# Hutschienenmoped_12V.net
KiCad netlist of a schematic drawn in EAGLE
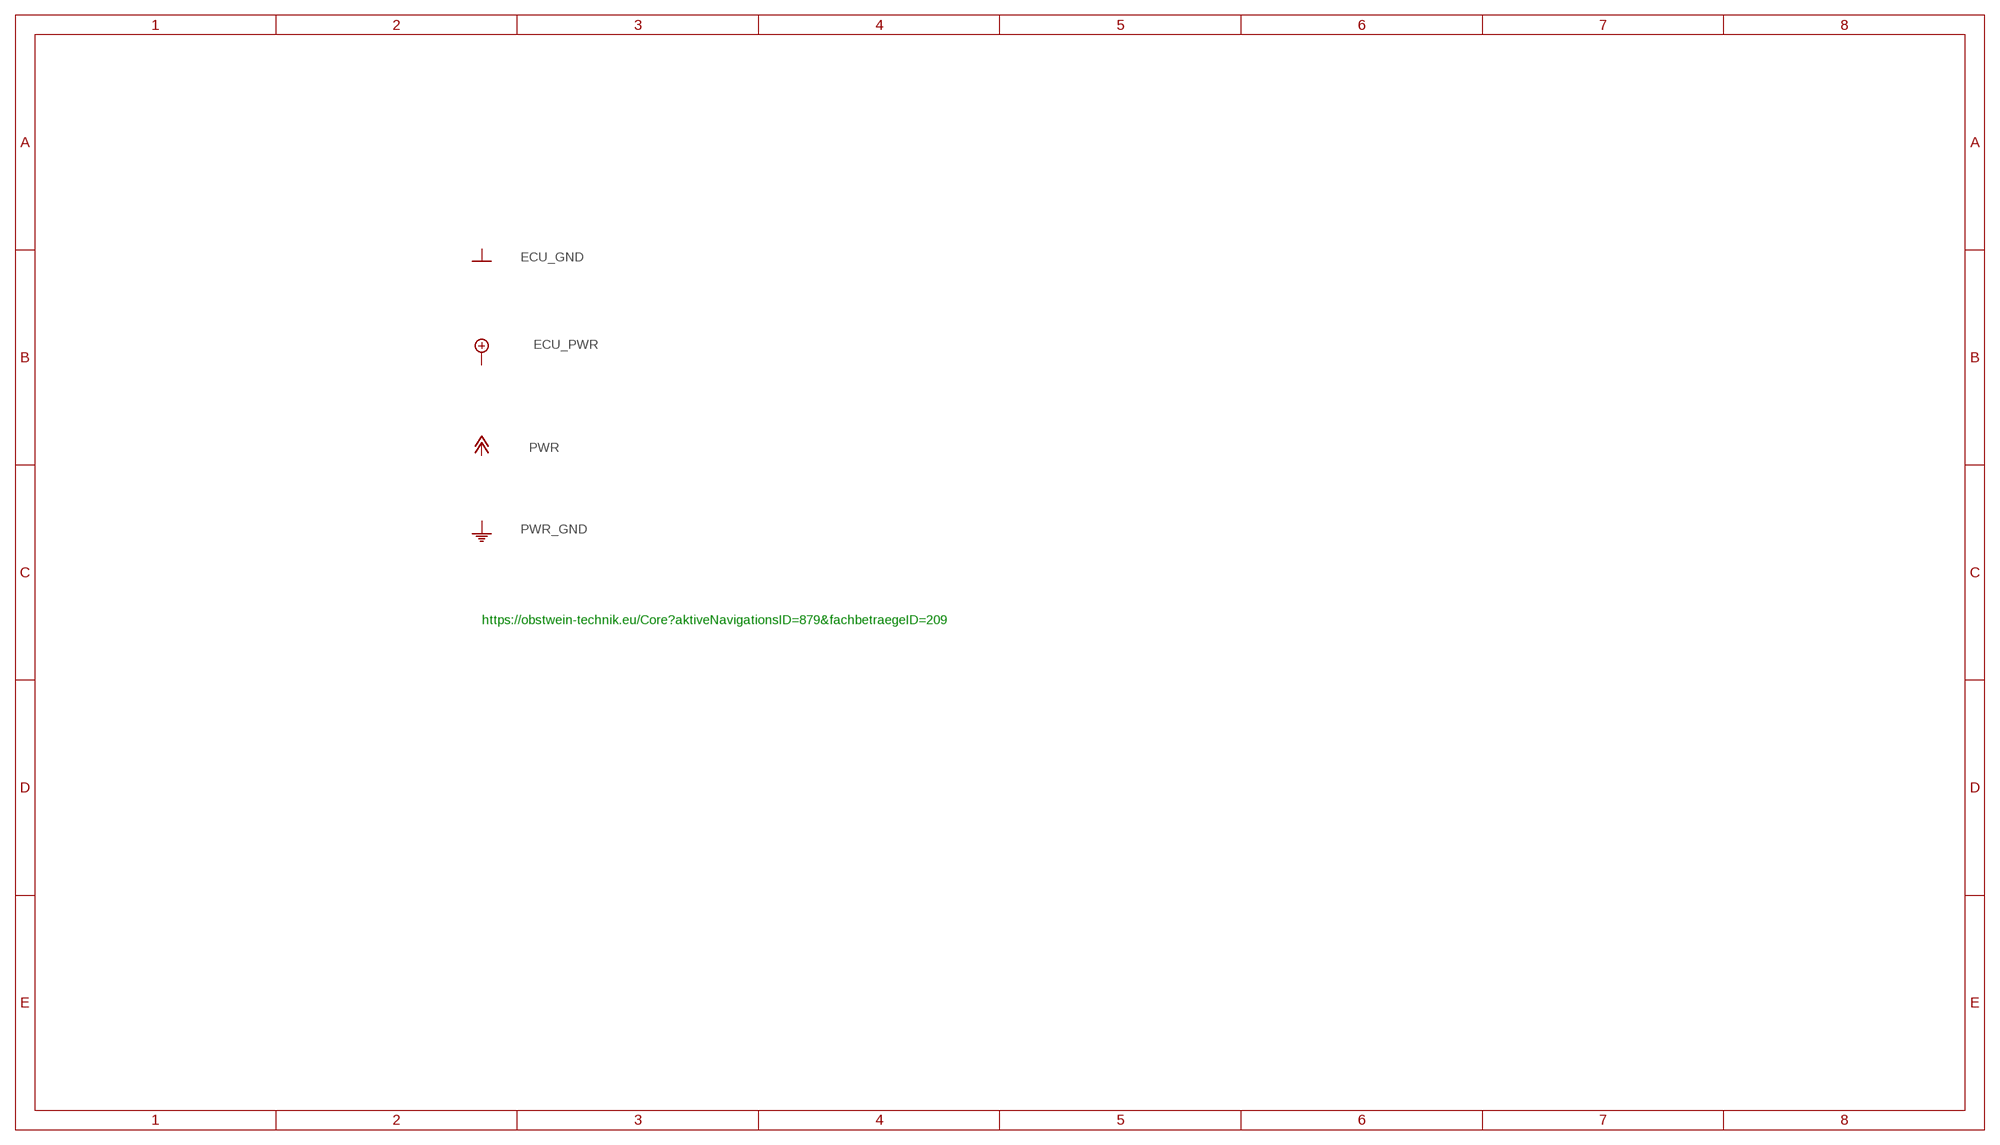
[diagram p0: schematic, sheet 1]
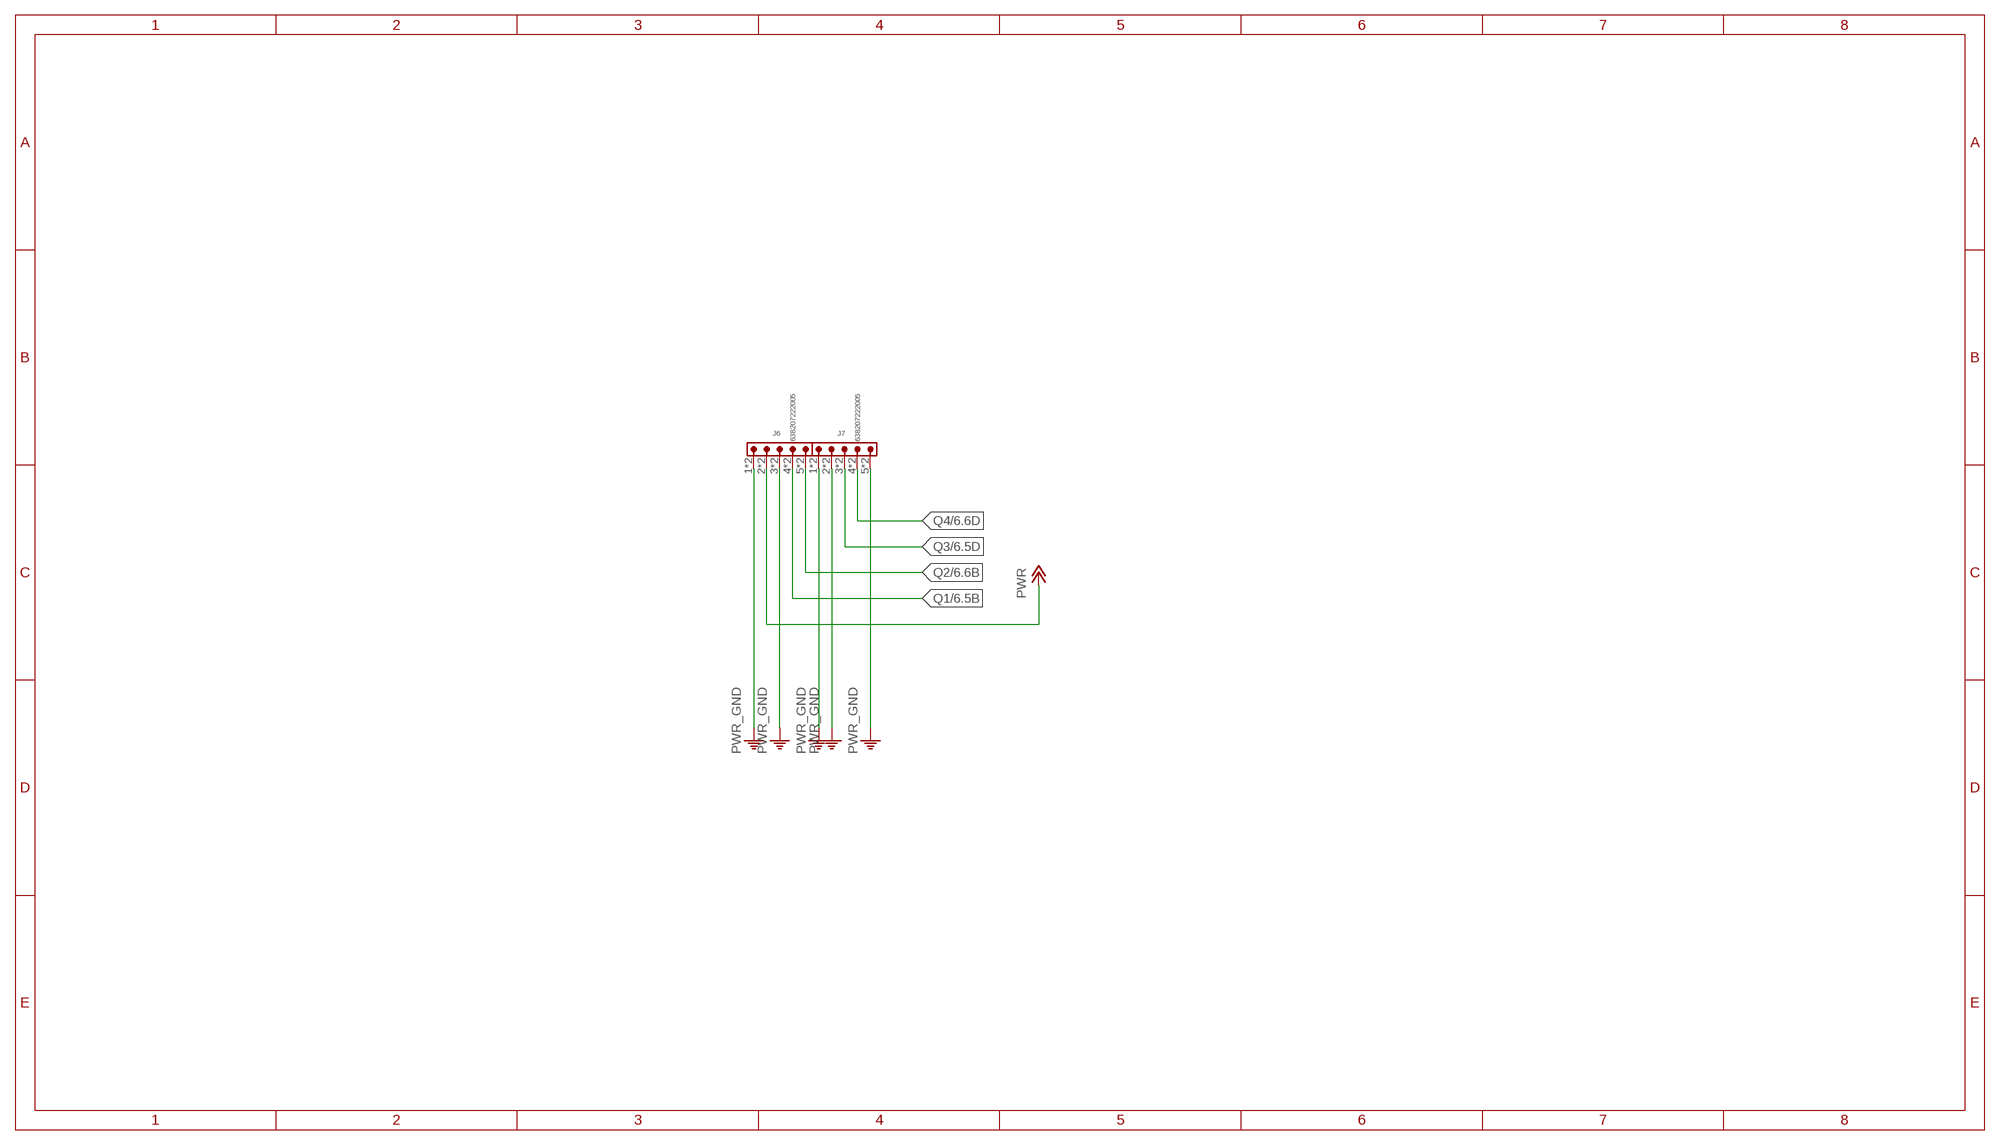
[diagram p1: schematic, sheet 2]
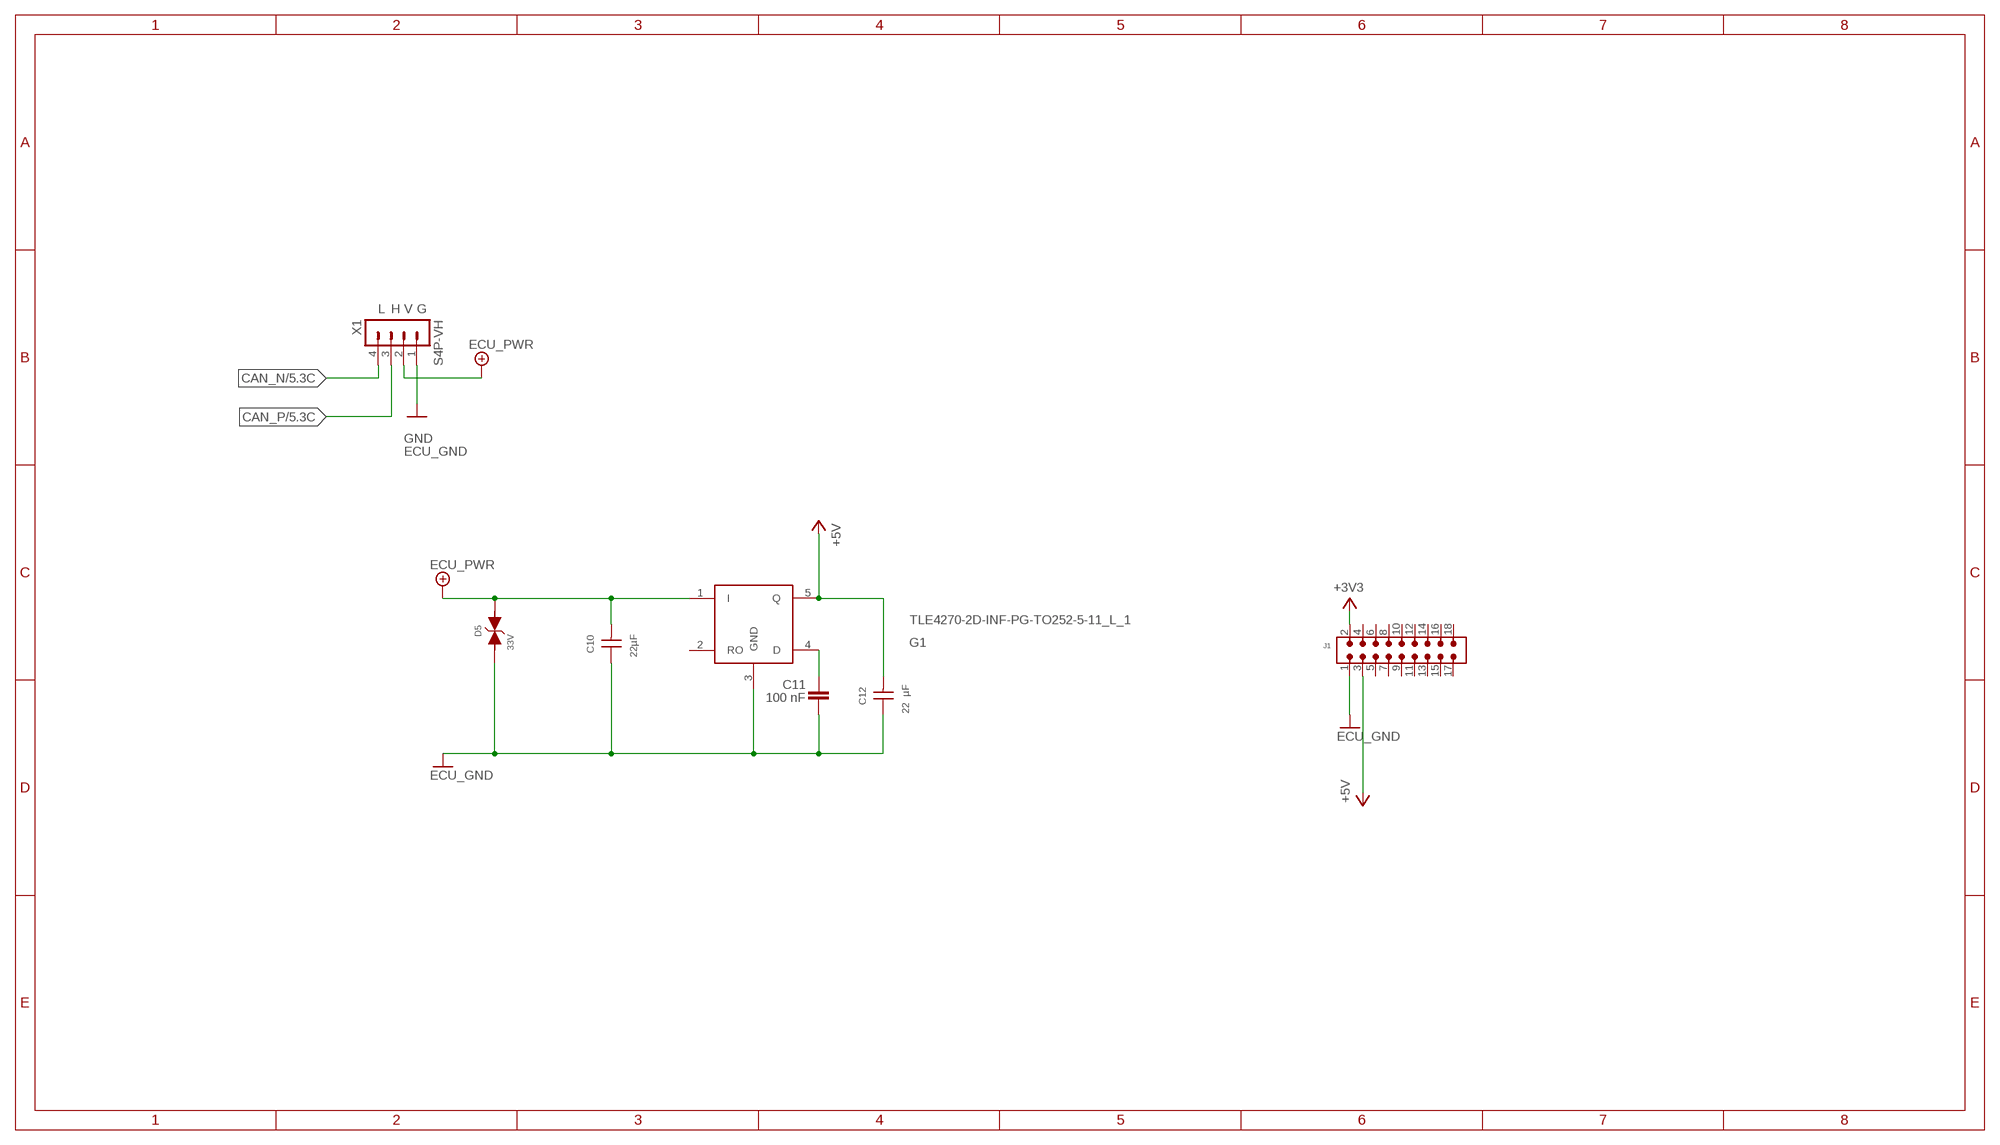
[diagram p2: schematic, sheet 3]
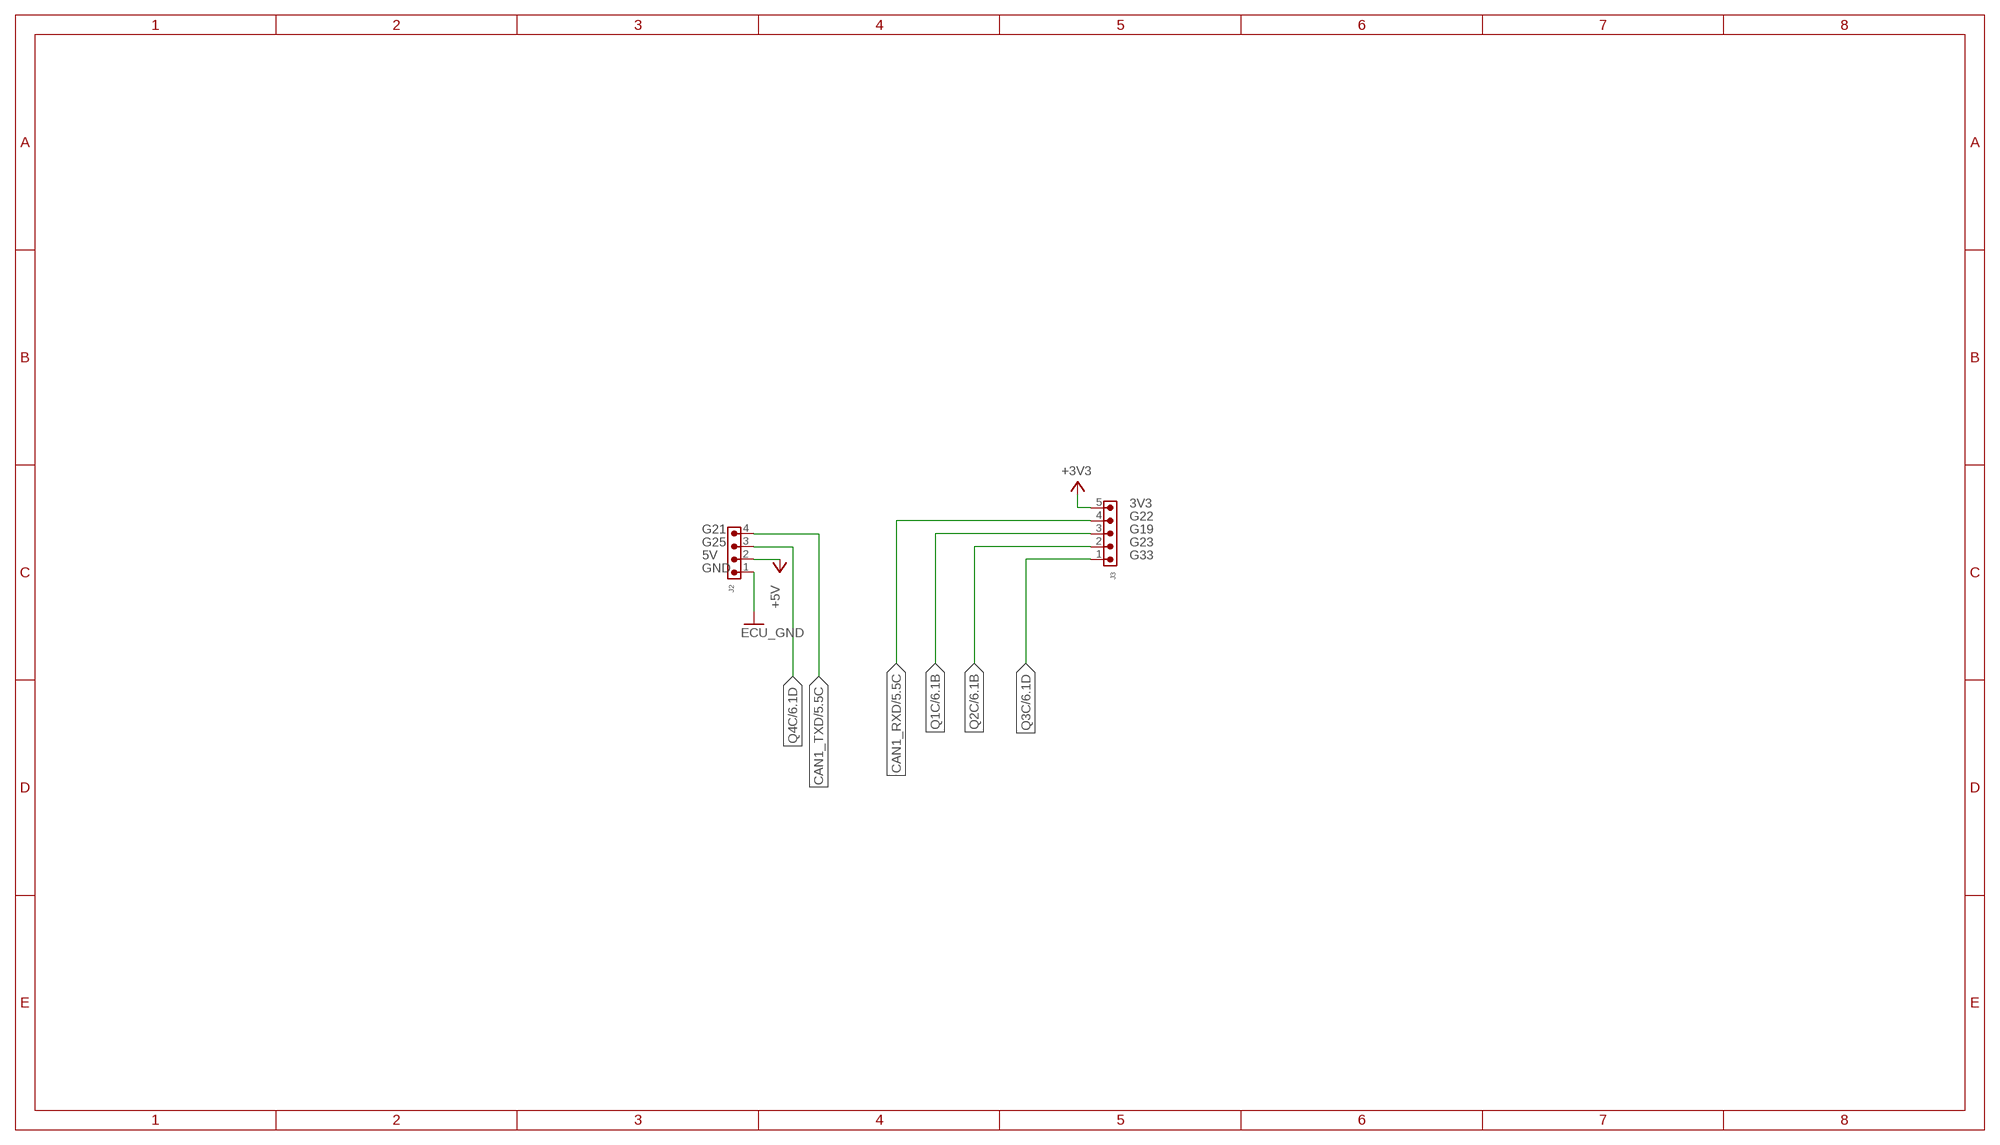
[diagram p3: schematic, sheet 4]
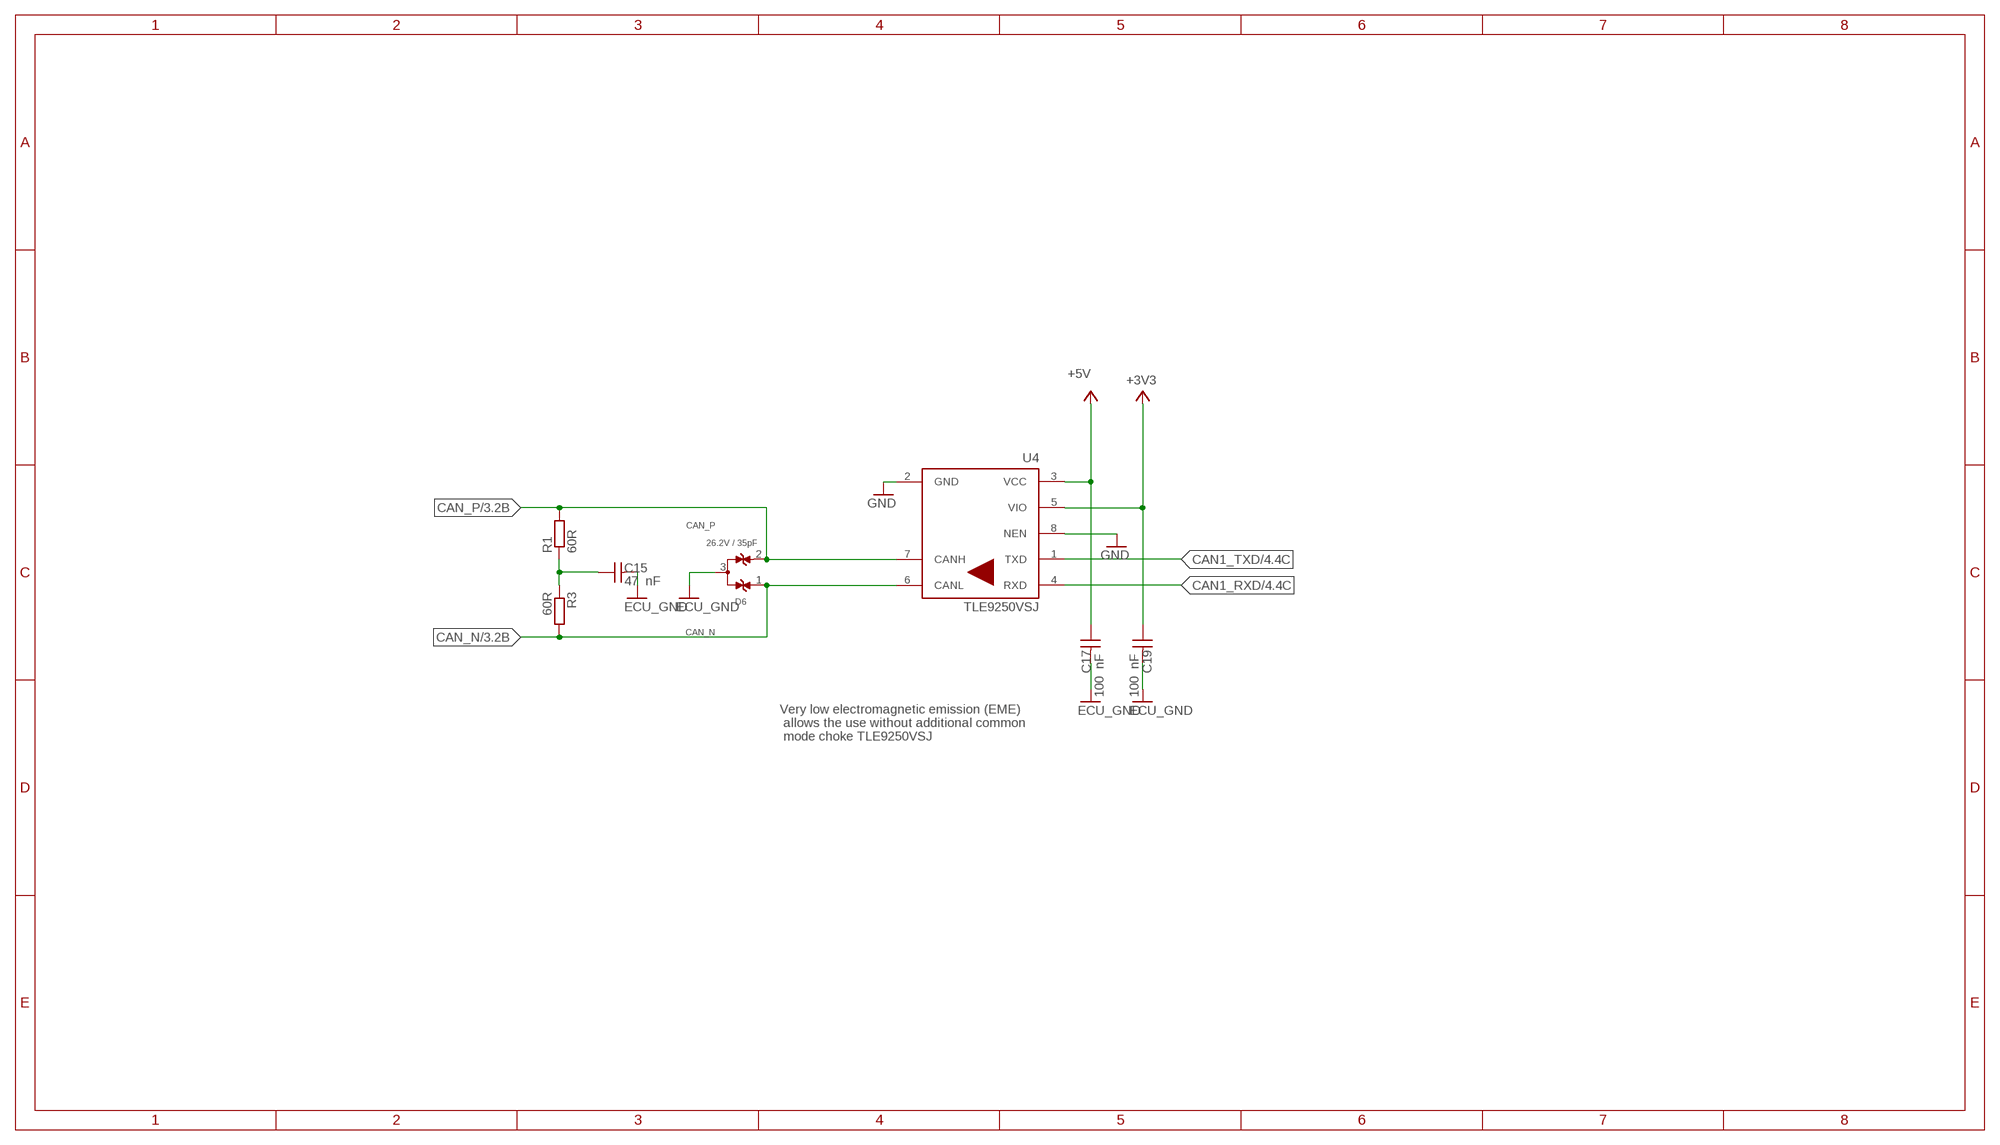
[diagram p4: schematic, sheet 5]
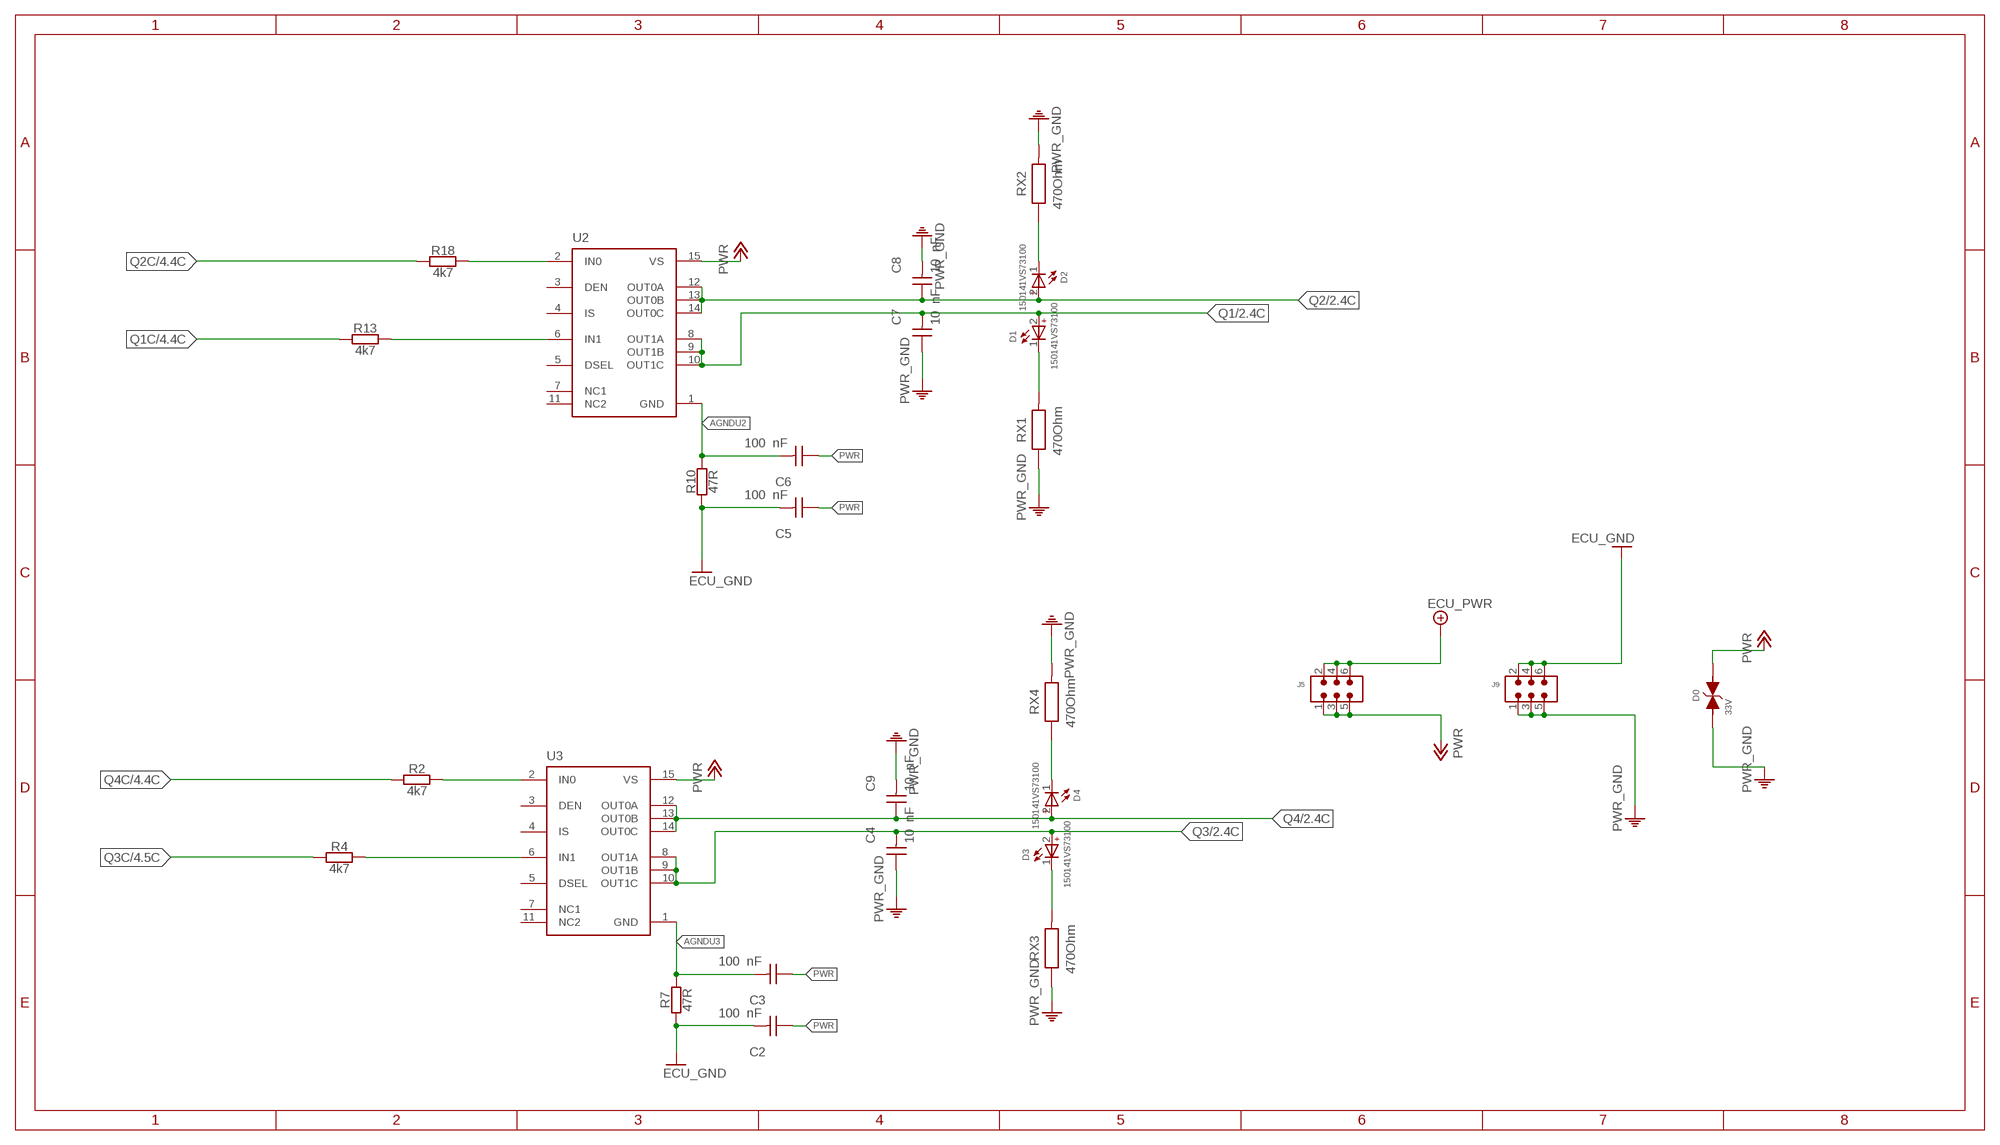
[diagram p5: schematic, sheet 6]

(export (version "E")
  (design (tool "Eeschema 10.0.6"))
  (components
    (comp (ref "C10")
      (value "22µF")
      (footprint "eagle-import:WCAP-CSGP_1210_H2.5")
      (libsource (lib "eagle-import") (part "WCAP-CSGP_1210_H2.5_25V(DC)_885012109014"))
    )
    (comp (ref "C11")
      (value "100 nF")
      (footprint "eagle-import:WCAP-CSGP_0402")
      (libsource (lib "eagle-import") (part "WCAP-CSGP_0402_16V(DC)_885012205037"))
    )
    (comp (ref "C12")
      (value "22 µF")
      (footprint "eagle-import:WCAP-CSGP_0805_H1.25_R")
      (libsource (lib "eagle-import") (part "WCAP-CSGP_0805_H1.25_10V(DC)_885012107011"))
    )
    (comp (ref "D5")
      (value "33V")
      (footprint "eagle-import:WE-TVSP_DO-214AB_BIDIRECTIONAL")
      (libsource (lib "eagle-import") (part "WE-TVSP_DO-214AB_3000W_BI_824551331"))
    )
    (comp (ref "G1")
      (value "TLE4270-2D-INF-PG-TO252-5-11_L_1")
      (footprint "eagle-import:INF-PG-TO252-5-11_L_1PRIMARY")
      (libsource (lib "eagle-import") (part "TLE4270-2D-INF-PG-TO252-5-11_L_1"))
    )
    (comp (ref "J1")
      (value "6130XX21121_61301821121")
      (footprint "eagle-import:61301821121")
      (libsource (lib "eagle-import") (part "6130XX21121_61301821121"))
    )
    (comp (ref "X1")
      (value "S4P-VH")
      (footprint "eagle-import:S4P-VH")
      (libsource (lib "eagle-import") (part "S4P-VH"))
    )
    (comp (ref "J6")
      (value "638207222005")
      (footprint "eagle-import:638207222005")
      (libsource (lib "eagle-import") (part "638207222005"))
    )
    (comp (ref "J7")
      (value "638207222005")
      (footprint "eagle-import:638207222005")
      (libsource (lib "eagle-import") (part "638207222005"))
    )
    (comp (ref "C2")
      (value "100 nF")
      (footprint "eagle-import:WCAP-CSGP_0805_H0.8_R")
      (libsource (lib "eagle-import") (part "WCAP-CSGP_0805_H0.8_50V(DC)_R_885012207098"))
    )
    (comp (ref "C3")
      (value "100 nF")
      (footprint "eagle-import:WCAP-CSGP_0805_H0.8_R")
      (libsource (lib "eagle-import") (part "WCAP-CSGP_0805_H0.8_50V(DC)_R_885012207098"))
    )
    (comp (ref "C4")
      (value "10 nF")
      (footprint "eagle-import:WCAP-CSGP_0805_H0.8_R")
      (libsource (lib "eagle-import") (part "WCAP-CSGP_0805_H0.8_50V(DC)_R_885012207092"))
    )
    (comp (ref "C5")
      (value "100 nF")
      (footprint "eagle-import:WCAP-CSGP_0805_H0.8_R")
      (libsource (lib "eagle-import") (part "WCAP-CSGP_0805_H0.8_50V(DC)_R_885012207098"))
    )
    (comp (ref "C6")
      (value "100 nF")
      (footprint "eagle-import:WCAP-CSGP_0805_H0.8_R")
      (libsource (lib "eagle-import") (part "WCAP-CSGP_0805_H0.8_50V(DC)_R_885012207098"))
    )
    (comp (ref "C7")
      (value "10 nF")
      (footprint "eagle-import:WCAP-CSGP_0805_H0.8_R")
      (libsource (lib "eagle-import") (part "WCAP-CSGP_0805_H0.8_50V(DC)_R_885012207092"))
    )
    (comp (ref "C8")
      (value "10 nF")
      (footprint "eagle-import:WCAP-CSGP_0805_H0.8_R")
      (libsource (lib "eagle-import") (part "WCAP-CSGP_0805_H0.8_50V(DC)_R_885012207092"))
    )
    (comp (ref "C9")
      (value "10 nF")
      (footprint "eagle-import:WCAP-CSGP_0805_H0.8_R")
      (libsource (lib "eagle-import") (part "WCAP-CSGP_0805_H0.8_50V(DC)_R_885012207092"))
    )
    (comp (ref "D0")
      (value "33V")
      (footprint "eagle-import:WE-TVSP_DO-214AB_BIDIRECTIONAL")
      (libsource (lib "eagle-import") (part "WE-TVSP_DO-214AB_3000W_BI_824551331"))
    )
    (comp (ref "D1")
      (value "150141VS73100")
      (footprint "eagle-import:WL-SMTW_3528")
      (libsource (lib "eagle-import") (part "WL-SMTW_3528_150141VS73100"))
    )
    (comp (ref "D2")
      (value "150141VS73100")
      (footprint "eagle-import:WL-SMTW_3528")
      (libsource (lib "eagle-import") (part "WL-SMTW_3528_150141VS73100"))
    )
    (comp (ref "D3")
      (value "150141VS73100")
      (footprint "eagle-import:WL-SMTW_3528")
      (libsource (lib "eagle-import") (part "WL-SMTW_3528_150141VS73100"))
    )
    (comp (ref "D4")
      (value "150141VS73100")
      (footprint "eagle-import:WL-SMTW_3528")
      (libsource (lib "eagle-import") (part "WL-SMTW_3528_150141VS73100"))
    )
    (comp (ref "J5")
      (value "6130XX21121_61300621121")
      (footprint "eagle-import:61300621121")
      (libsource (lib "eagle-import") (part "6130XX21121_61300621121"))
    )
    (comp (ref "J9")
      (value "6130XX21121_61300621121")
      (footprint "eagle-import:61300621121")
      (libsource (lib "eagle-import") (part "6130XX21121_61300621121"))
    )
    (comp (ref "R2")
      (value "4k7")
      (footprint "eagle-import:R0805")
      (libsource (lib "eagle-import") (part "R-EU_R0805"))
    )
    (comp (ref "R4")
      (value "4k7")
      (footprint "eagle-import:R0805")
      (libsource (lib "eagle-import") (part "R-EU_R0805"))
    )
    (comp (ref "R7")
      (value "47R")
      (footprint "eagle-import:R0805")
      (libsource (lib "eagle-import") (part "R-EU_R0805"))
    )
    (comp (ref "R10")
      (value "47R")
      (footprint "eagle-import:R0805")
      (libsource (lib "eagle-import") (part "R-EU_R0805"))
    )
    (comp (ref "R13")
      (value "4k7")
      (footprint "eagle-import:R0805")
      (libsource (lib "eagle-import") (part "R-EU_R0805"))
    )
    (comp (ref "R18")
      (value "4k7")
      (footprint "eagle-import:R0805")
      (libsource (lib "eagle-import") (part "R-EU_R0805"))
    )
    (comp (ref "RX1")
      (value "470Ohm")
      (footprint "eagle-import:WRIS-KWKB_0612")
      (libsource (lib "eagle-import") (part "WRIS-KWKB_0612_561020132023"))
    )
    (comp (ref "RX2")
      (value "470Ohm")
      (footprint "eagle-import:WRIS-KWKB_0612")
      (libsource (lib "eagle-import") (part "WRIS-KWKB_0612_561020132023"))
    )
    (comp (ref "RX3")
      (value "470Ohm")
      (footprint "eagle-import:WRIS-KWKB_0612")
      (libsource (lib "eagle-import") (part "WRIS-KWKB_0612_561020132023"))
    )
    (comp (ref "RX4")
      (value "470Ohm")
      (footprint "eagle-import:WRIS-KWKB_0612")
      (libsource (lib "eagle-import") (part "WRIS-KWKB_0612_561020132023"))
    )
    (comp (ref "U2")
      (value "BTS7030-2EPA")
      (footprint "eagle-import:SOP65P600X115-15N-V")
      (libsource (lib "eagle-import") (part "BTS7030-2EPA"))
    )
    (comp (ref "U3")
      (value "BTS7030-2EPA")
      (footprint "eagle-import:SOP65P600X115-15N-V")
      (libsource (lib "eagle-import") (part "BTS7030-2EPA"))
    )
    (comp (ref "C15")
      (value "47 nF")
      (footprint "eagle-import:WCAP-CSGP_0805_H0.8_R")
      (libsource (lib "eagle-import") (part "WCAP-CSGP_0805_H0.8_50V(DC)_R_885012207096"))
    )
    (comp (ref "C17")
      (value "100 nF")
      (footprint "eagle-import:WCAP-CSGP_0805_H0.8_R")
      (libsource (lib "eagle-import") (part "WCAP-CSGP_0805_H0.8_50V(DC)_R_885012207098"))
    )
    (comp (ref "C19")
      (value "100 nF")
      (footprint "eagle-import:WCAP-CSGP_0805_H0.8_R")
      (libsource (lib "eagle-import") (part "WCAP-CSGP_0805_H0.8_50V(DC)_R_885012207098"))
    )
    (comp (ref "D6")
      (value "26.2V / 35pF")
      (footprint "eagle-import:WE-TVS_SOT23-3L")
      (libsource (lib "eagle-import") (part "WE-TVS_SOT23-3L_824098024"))
    )
    (comp (ref "R1")
      (value "60R")
      (footprint "eagle-import:R0805")
      (libsource (lib "eagle-import") (part "R-EU_R0805"))
    )
    (comp (ref "R3")
      (value "60R")
      (footprint "eagle-import:R0805")
      (libsource (lib "eagle-import") (part "R-EU_R0805"))
    )
    (comp (ref "U4")
      (value "TLE9250VSJ")
      (footprint "eagle-import:SOIC127P602X173-8N-V")
      (libsource (lib "eagle-import") (part "TLE9250VSJ"))
    )
    (comp (ref "J2")
      (value "6130XX11121_61300411121")
      (footprint "eagle-import:61300411121")
      (libsource (lib "eagle-import") (part "6130XX11121_61300411121"))
    )
    (comp (ref "J3")
      (value "6130XX11121_61300511121")
      (footprint "eagle-import:61300511121")
      (libsource (lib "eagle-import") (part "6130XX11121_61300511121"))
    )
  )
  (nets
    (net (code "1") (name "+3V3") (class "Default")
      (node (ref "C19") (pin "1") (pinfunction "1_1") (pintype "passive"))
      (node (ref "J1") (pin "2") (pinfunction "2_2") (pintype "passive"))
      (node (ref "J3") (pin "5") (pinfunction "5_5") (pintype "passive"))
      (node (ref "U4") (pin "5") (pinfunction "VIO_5") (pintype "input"))
    )
    (net (code "2") (name "+5V") (class "Default")
      (node (ref "C12") (pin "2") (pinfunction "2_2") (pintype "passive"))
      (node (ref "C17") (pin "1") (pinfunction "1_1") (pintype "passive"))
      (node (ref "G1") (pin "5") (pinfunction "Q_5") (pintype "power_in"))
      (node (ref "J1") (pin "3") (pinfunction "3_3") (pintype "passive"))
      (node (ref "J2") (pin "2") (pinfunction "2_2") (pintype "passive"))
      (node (ref "U4") (pin "3") (pinfunction "VCC_3") (pintype "input"))
    )
    (net (code "3") (name "AGNDU2") (class "Default")
      (node (ref "C6") (pin "2") (pinfunction "2_2") (pintype "passive"))
      (node (ref "R10") (pin "2") (pinfunction "2_2") (pintype "passive"))
      (node (ref "U2") (pin "1") (pinfunction "GND_1") (pintype "power_in"))
    )
    (net (code "4") (name "AGNDU3") (class "Default")
      (node (ref "C3") (pin "2") (pinfunction "2_2") (pintype "passive"))
      (node (ref "R7") (pin "2") (pinfunction "2_2") (pintype "passive"))
      (node (ref "U3") (pin "1") (pinfunction "GND_1") (pintype "power_in"))
    )
    (net (code "5") (name "CAN1_RXD") (class "Default")
      (node (ref "J3") (pin "4") (pinfunction "4_4") (pintype "passive"))
      (node (ref "U4") (pin "4") (pinfunction "RXD_4") (pintype "output"))
    )
    (net (code "6") (name "CAN1_TXD") (class "Default")
      (node (ref "J2") (pin "4") (pinfunction "4_4") (pintype "passive"))
      (node (ref "U4") (pin "1") (pinfunction "TXD_1") (pintype "input"))
    )
    (net (code "7") (name "CAN_N") (class "Default")
      (node (ref "D6") (pin "1") (pinfunction "1_1") (pintype "passive"))
      (node (ref "R3") (pin "2") (pinfunction "2_2") (pintype "passive"))
      (node (ref "U4") (pin "6") (pinfunction "CANL_6") (pintype "bidirectional"))
      (node (ref "X1") (pin "4") (pinfunction "4_4") (pintype "passive"))
    )
    (net (code "8") (name "CAN_P") (class "Default")
      (node (ref "D6") (pin "2") (pinfunction "2_2") (pintype "passive"))
      (node (ref "R1") (pin "2") (pinfunction "2_2") (pintype "passive"))
      (node (ref "U4") (pin "7") (pinfunction "CANH_7") (pintype "bidirectional"))
      (node (ref "X1") (pin "3") (pinfunction "3_3") (pintype "passive"))
    )
    (net (code "9") (name "ECU_GND") (class "Default")
      (node (ref "C10") (pin "1") (pinfunction "1_1") (pintype "passive"))
      (node (ref "C11") (pin "2") (pinfunction "2_2") (pintype "passive"))
      (node (ref "C12") (pin "1") (pinfunction "1_1") (pintype "passive"))
      (node (ref "C15") (pin "2") (pinfunction "2_2") (pintype "passive"))
      (node (ref "C17") (pin "2") (pinfunction "2_2") (pintype "passive"))
      (node (ref "C19") (pin "2") (pinfunction "2_2") (pintype "passive"))
      (node (ref "C2") (pin "2") (pinfunction "2_2") (pintype "passive"))
      (node (ref "C5") (pin "2") (pinfunction "2_2") (pintype "passive"))
      (node (ref "D5") (pin "1") (pinfunction "1_1") (pintype "passive"))
      (node (ref "D6") (pin "3") (pinfunction "3_3") (pintype "passive"))
      (node (ref "G1") (pin "3") (pinfunction "GND_3") (pintype "power_in"))
      (node (ref "J1") (pin "1") (pinfunction "1_1") (pintype "passive"))
      (node (ref "J2") (pin "1") (pinfunction "1_1") (pintype "passive"))
      (node (ref "J9") (pin "2") (pinfunction "2_2") (pintype "passive"))
      (node (ref "J9") (pin "4") (pinfunction "4_4") (pintype "passive"))
      (node (ref "J9") (pin "6") (pinfunction "6_6") (pintype "passive"))
      (node (ref "R10") (pin "1") (pinfunction "1_1") (pintype "passive"))
      (node (ref "R7") (pin "1") (pinfunction "1_1") (pintype "passive"))
      (node (ref "U4") (pin "2") (pinfunction "GND_2") (pintype "power_in"))
      (node (ref "U4") (pin "8") (pinfunction "NEN_8") (pintype "input"))
      (node (ref "X1") (pin "1") (pinfunction "1_1") (pintype "passive"))
    )
    (net (code "10") (name "ECU_PWR") (class "Default")
      (node (ref "C10") (pin "2") (pinfunction "2_2") (pintype "passive"))
      (node (ref "D5") (pin "2") (pinfunction "2_2") (pintype "passive"))
      (node (ref "G1") (pin "1") (pinfunction "I_1") (pintype "power_in"))
      (node (ref "J5") (pin "2") (pinfunction "2_2") (pintype "passive"))
      (node (ref "J5") (pin "4") (pinfunction "4_4") (pintype "passive"))
      (node (ref "J5") (pin "6") (pinfunction "6_6") (pintype "passive"))
      (node (ref "X1") (pin "2") (pinfunction "2_2") (pintype "passive"))
    )
    (net (code "11") (name "Net-(C15-Pad1)") (class "Default")
      (node (ref "C15") (pin "1") (pinfunction "1_1") (pintype "passive"))
      (node (ref "R1") (pin "1") (pinfunction "1_1") (pintype "passive"))
      (node (ref "R3") (pin "1") (pinfunction "1_1") (pintype "passive"))
    )
    (net (code "12") (name "Net-(D1--)") (class "Default")
      (node (ref "D1") (pin "1") (pinfunction "-_1") (pintype "passive"))
      (node (ref "RX1") (pin "2") (pinfunction "2_2") (pintype "passive"))
    )
    (net (code "13") (name "Net-(D2--)") (class "Default")
      (node (ref "D2") (pin "1") (pinfunction "-_1") (pintype "passive"))
      (node (ref "RX2") (pin "1") (pinfunction "1_1") (pintype "passive"))
    )
    (net (code "14") (name "Net-(D3--)") (class "Default")
      (node (ref "D3") (pin "1") (pinfunction "-_1") (pintype "passive"))
      (node (ref "RX3") (pin "2") (pinfunction "2_2") (pintype "passive"))
    )
    (net (code "15") (name "Net-(D4--)") (class "Default")
      (node (ref "D4") (pin "1") (pinfunction "-_1") (pintype "passive"))
      (node (ref "RX4") (pin "1") (pinfunction "1_1") (pintype "passive"))
    )
    (net (code "16") (name "Net-(G1-D)") (class "Default")
      (node (ref "C11") (pin "1") (pinfunction "1_1") (pintype "passive"))
      (node (ref "G1") (pin "4") (pinfunction "D_4") (pintype "bidirectional"))
    )
    (net (code "17") (name "Net-(U2-IN0)") (class "Default")
      (node (ref "R18") (pin "2") (pinfunction "2_2") (pintype "passive"))
      (node (ref "U2") (pin "2") (pinfunction "IN0_2") (pintype "input"))
    )
    (net (code "18") (name "Net-(U2-IN1)") (class "Default")
      (node (ref "R13") (pin "2") (pinfunction "2_2") (pintype "passive"))
      (node (ref "U2") (pin "6") (pinfunction "IN1_6") (pintype "input"))
    )
    (net (code "19") (name "Net-(U3-IN0)") (class "Default")
      (node (ref "R2") (pin "2") (pinfunction "2_2") (pintype "passive"))
      (node (ref "U3") (pin "2") (pinfunction "IN0_2") (pintype "input"))
    )
    (net (code "20") (name "Net-(U3-IN1)") (class "Default")
      (node (ref "R4") (pin "2") (pinfunction "2_2") (pintype "passive"))
      (node (ref "U3") (pin "6") (pinfunction "IN1_6") (pintype "input"))
    )
    (net (code "21") (name "PWR") (class "Default")
      (node (ref "C2") (pin "1") (pinfunction "1_1") (pintype "passive"))
      (node (ref "C3") (pin "1") (pinfunction "1_1") (pintype "passive"))
      (node (ref "C5") (pin "1") (pinfunction "1_1") (pintype "passive"))
      (node (ref "C6") (pin "1") (pinfunction "1_1") (pintype "passive"))
      (node (ref "D0") (pin "2") (pinfunction "2_2") (pintype "passive"))
      (node (ref "J5") (pin "1") (pinfunction "1_1") (pintype "passive"))
      (node (ref "J5") (pin "3") (pinfunction "3_3") (pintype "passive"))
      (node (ref "J5") (pin "5") (pinfunction "5_5") (pintype "passive"))
      (node (ref "J6") (pin "2") (pinfunction "2_2") (pintype "passive"))
      (node (ref "J6") (pin "A2") (pinfunction "2_A2") (pintype "passive"))
      (node (ref "U2") (pin "15") (pinfunction "VS_15") (pintype "power_in"))
      (node (ref "U3") (pin "15") (pinfunction "VS_15") (pintype "power_in"))
    )
    (net (code "22") (name "PWR_GND") (class "Default")
      (node (ref "C4") (pin "1") (pinfunction "1_1") (pintype "passive"))
      (node (ref "C7") (pin "1") (pinfunction "1_1") (pintype "passive"))
      (node (ref "C8") (pin "2") (pinfunction "2_2") (pintype "passive"))
      (node (ref "C9") (pin "2") (pinfunction "2_2") (pintype "passive"))
      (node (ref "D0") (pin "1") (pinfunction "1_1") (pintype "passive"))
      (node (ref "J6") (pin "1") (pinfunction "1_1") (pintype "passive"))
      (node (ref "J6") (pin "3") (pinfunction "3_3") (pintype "passive"))
      (node (ref "J6") (pin "A1") (pinfunction "1_A1") (pintype "passive"))
      (node (ref "J6") (pin "A3") (pinfunction "3_A3") (pintype "passive"))
      (node (ref "J7") (pin "1") (pinfunction "1_1") (pintype "passive"))
      (node (ref "J7") (pin "2") (pinfunction "2_2") (pintype "passive"))
      (node (ref "J7") (pin "5") (pinfunction "5_5") (pintype "passive"))
      (node (ref "J7") (pin "A1") (pinfunction "1_A1") (pintype "passive"))
      (node (ref "J7") (pin "A2") (pinfunction "2_A2") (pintype "passive"))
      (node (ref "J7") (pin "A5") (pinfunction "5_A5") (pintype "passive"))
      (node (ref "J9") (pin "1") (pinfunction "1_1") (pintype "passive"))
      (node (ref "J9") (pin "3") (pinfunction "3_3") (pintype "passive"))
      (node (ref "J9") (pin "5") (pinfunction "5_5") (pintype "passive"))
      (node (ref "RX1") (pin "1") (pinfunction "1_1") (pintype "passive"))
      (node (ref "RX2") (pin "2") (pinfunction "2_2") (pintype "passive"))
      (node (ref "RX3") (pin "1") (pinfunction "1_1") (pintype "passive"))
      (node (ref "RX4") (pin "2") (pinfunction "2_2") (pintype "passive"))
    )
    (net (code "23") (name "Q1") (class "Default")
      (node (ref "C7") (pin "2") (pinfunction "2_2") (pintype "passive"))
      (node (ref "D1") (pin "2") (pinfunction "+_2") (pintype "passive"))
      (node (ref "J6") (pin "4") (pinfunction "4_4") (pintype "passive"))
      (node (ref "J6") (pin "A4") (pinfunction "4_A4") (pintype "passive"))
      (node (ref "U2") (pin "10") (pinfunction "OUT1C_10") (pintype "output"))
      (node (ref "U2") (pin "8") (pinfunction "OUT1A_8") (pintype "output"))
      (node (ref "U2") (pin "9") (pinfunction "OUT1B_9") (pintype "output"))
    )
    (net (code "24") (name "Q1C") (class "Default")
      (node (ref "J3") (pin "3") (pinfunction "3_3") (pintype "passive"))
      (node (ref "R13") (pin "1") (pinfunction "1_1") (pintype "passive"))
    )
    (net (code "25") (name "Q2") (class "Default")
      (node (ref "C8") (pin "1") (pinfunction "1_1") (pintype "passive"))
      (node (ref "D2") (pin "2") (pinfunction "+_2") (pintype "passive"))
      (node (ref "J6") (pin "5") (pinfunction "5_5") (pintype "passive"))
      (node (ref "J6") (pin "A5") (pinfunction "5_A5") (pintype "passive"))
      (node (ref "U2") (pin "12") (pinfunction "OUT0A_12") (pintype "output"))
      (node (ref "U2") (pin "13") (pinfunction "OUT0B_13") (pintype "output"))
      (node (ref "U2") (pin "14") (pinfunction "OUT0C_14") (pintype "output"))
    )
    (net (code "26") (name "Q2C") (class "Default")
      (node (ref "J3") (pin "2") (pinfunction "2_2") (pintype "passive"))
      (node (ref "R18") (pin "1") (pinfunction "1_1") (pintype "passive"))
    )
    (net (code "27") (name "Q3") (class "Default")
      (node (ref "C4") (pin "2") (pinfunction "2_2") (pintype "passive"))
      (node (ref "D3") (pin "2") (pinfunction "+_2") (pintype "passive"))
      (node (ref "J7") (pin "3") (pinfunction "3_3") (pintype "passive"))
      (node (ref "J7") (pin "A3") (pinfunction "3_A3") (pintype "passive"))
      (node (ref "U3") (pin "10") (pinfunction "OUT1C_10") (pintype "output"))
      (node (ref "U3") (pin "8") (pinfunction "OUT1A_8") (pintype "output"))
      (node (ref "U3") (pin "9") (pinfunction "OUT1B_9") (pintype "output"))
    )
    (net (code "28") (name "Q3C") (class "Default")
      (node (ref "J3") (pin "1") (pinfunction "1_1") (pintype "passive"))
      (node (ref "R4") (pin "1") (pinfunction "1_1") (pintype "passive"))
    )
    (net (code "29") (name "Q4") (class "Default")
      (node (ref "C9") (pin "1") (pinfunction "1_1") (pintype "passive"))
      (node (ref "D4") (pin "2") (pinfunction "+_2") (pintype "passive"))
      (node (ref "J7") (pin "4") (pinfunction "4_4") (pintype "passive"))
      (node (ref "J7") (pin "A4") (pinfunction "4_A4") (pintype "passive"))
      (node (ref "U3") (pin "12") (pinfunction "OUT0A_12") (pintype "output"))
      (node (ref "U3") (pin "13") (pinfunction "OUT0B_13") (pintype "output"))
      (node (ref "U3") (pin "14") (pinfunction "OUT0C_14") (pintype "output"))
    )
    (net (code "30") (name "Q4C") (class "Default")
      (node (ref "J2") (pin "3") (pinfunction "3_3") (pintype "passive"))
      (node (ref "R2") (pin "1") (pinfunction "1_1") (pintype "passive"))
    )
    (net (code "31") (name "unconnected-(G1-RO-Pad2)") (class "Default")
      (node (ref "G1") (pin "2") (pinfunction "RO_2") (pintype "output"))
    )
    (net (code "32") (name "unconnected-(J1-Pad4)") (class "Default")
      (node (ref "J1") (pin "4") (pinfunction "4_4") (pintype "passive"))
    )
    (net (code "33") (name "unconnected-(J1-Pad5)") (class "Default")
      (node (ref "J1") (pin "5") (pinfunction "5_5") (pintype "passive"))
    )
    (net (code "34") (name "unconnected-(J1-Pad6)") (class "Default")
      (node (ref "J1") (pin "6") (pinfunction "6_6") (pintype "passive"))
    )
    (net (code "35") (name "unconnected-(J1-Pad7)") (class "Default")
      (node (ref "J1") (pin "7") (pinfunction "7_7") (pintype "passive"))
    )
    (net (code "36") (name "unconnected-(J1-Pad8)") (class "Default")
      (node (ref "J1") (pin "8") (pinfunction "8_8") (pintype "passive"))
    )
    (net (code "37") (name "unconnected-(J1-Pad9)") (class "Default")
      (node (ref "J1") (pin "9") (pinfunction "9_9") (pintype "passive"))
    )
    (net (code "38") (name "unconnected-(J1-Pad10)") (class "Default")
      (node (ref "J1") (pin "10") (pinfunction "10_10") (pintype "passive"))
    )
    (net (code "39") (name "unconnected-(J1-Pad11)") (class "Default")
      (node (ref "J1") (pin "11") (pinfunction "11_11") (pintype "passive"))
    )
    (net (code "40") (name "unconnected-(J1-Pad12)") (class "Default")
      (node (ref "J1") (pin "12") (pinfunction "12_12") (pintype "passive"))
    )
    (net (code "41") (name "unconnected-(J1-Pad13)") (class "Default")
      (node (ref "J1") (pin "13") (pinfunction "13_13") (pintype "passive"))
    )
    (net (code "42") (name "unconnected-(J1-Pad14)") (class "Default")
      (node (ref "J1") (pin "14") (pinfunction "14_14") (pintype "passive"))
    )
    (net (code "43") (name "unconnected-(J1-Pad15)") (class "Default")
      (node (ref "J1") (pin "15") (pinfunction "15_15") (pintype "passive"))
    )
    (net (code "44") (name "unconnected-(J1-Pad16)") (class "Default")
      (node (ref "J1") (pin "16") (pinfunction "16_16") (pintype "passive"))
    )
    (net (code "45") (name "unconnected-(J1-Pad17)") (class "Default")
      (node (ref "J1") (pin "17") (pinfunction "17_17") (pintype "passive"))
    )
    (net (code "46") (name "unconnected-(J1-Pad18)") (class "Default")
      (node (ref "J1") (pin "18") (pinfunction "18_18") (pintype "passive"))
    )
    (net (code "47") (name "unconnected-(U2-DEN-Pad3)") (class "Default")
      (node (ref "U2") (pin "3") (pinfunction "DEN_3") (pintype "input"))
    )
    (net (code "48") (name "unconnected-(U2-DSEL-Pad5)") (class "Default")
      (node (ref "U2") (pin "5") (pinfunction "DSEL_5") (pintype "input"))
    )
    (net (code "49") (name "unconnected-(U2-IS-Pad4)") (class "Default")
      (node (ref "U2") (pin "4") (pinfunction "IS_4") (pintype "output"))
    )
    (net (code "50") (name "unconnected-(U2-NC1-Pad7)") (class "Default")
      (node (ref "U2") (pin "7") (pinfunction "NC1_7") (pintype "passive"))
    )
    (net (code "51") (name "unconnected-(U2-NC2-Pad11)") (class "Default")
      (node (ref "U2") (pin "11") (pinfunction "NC2_11") (pintype "passive"))
    )
    (net (code "52") (name "unconnected-(U3-DEN-Pad3)") (class "Default")
      (node (ref "U3") (pin "3") (pinfunction "DEN_3") (pintype "input"))
    )
    (net (code "53") (name "unconnected-(U3-DSEL-Pad5)") (class "Default")
      (node (ref "U3") (pin "5") (pinfunction "DSEL_5") (pintype "input"))
    )
    (net (code "54") (name "unconnected-(U3-IS-Pad4)") (class "Default")
      (node (ref "U3") (pin "4") (pinfunction "IS_4") (pintype "output"))
    )
    (net (code "55") (name "unconnected-(U3-NC1-Pad7)") (class "Default")
      (node (ref "U3") (pin "7") (pinfunction "NC1_7") (pintype "passive"))
    )
    (net (code "56") (name "unconnected-(U3-NC2-Pad11)") (class "Default")
      (node (ref "U3") (pin "11") (pinfunction "NC2_11") (pintype "passive"))
    )
  )
)
